# MTL_BaroTact2D_V2.net
KiCad netlist of a schematic drawn in EAGLE
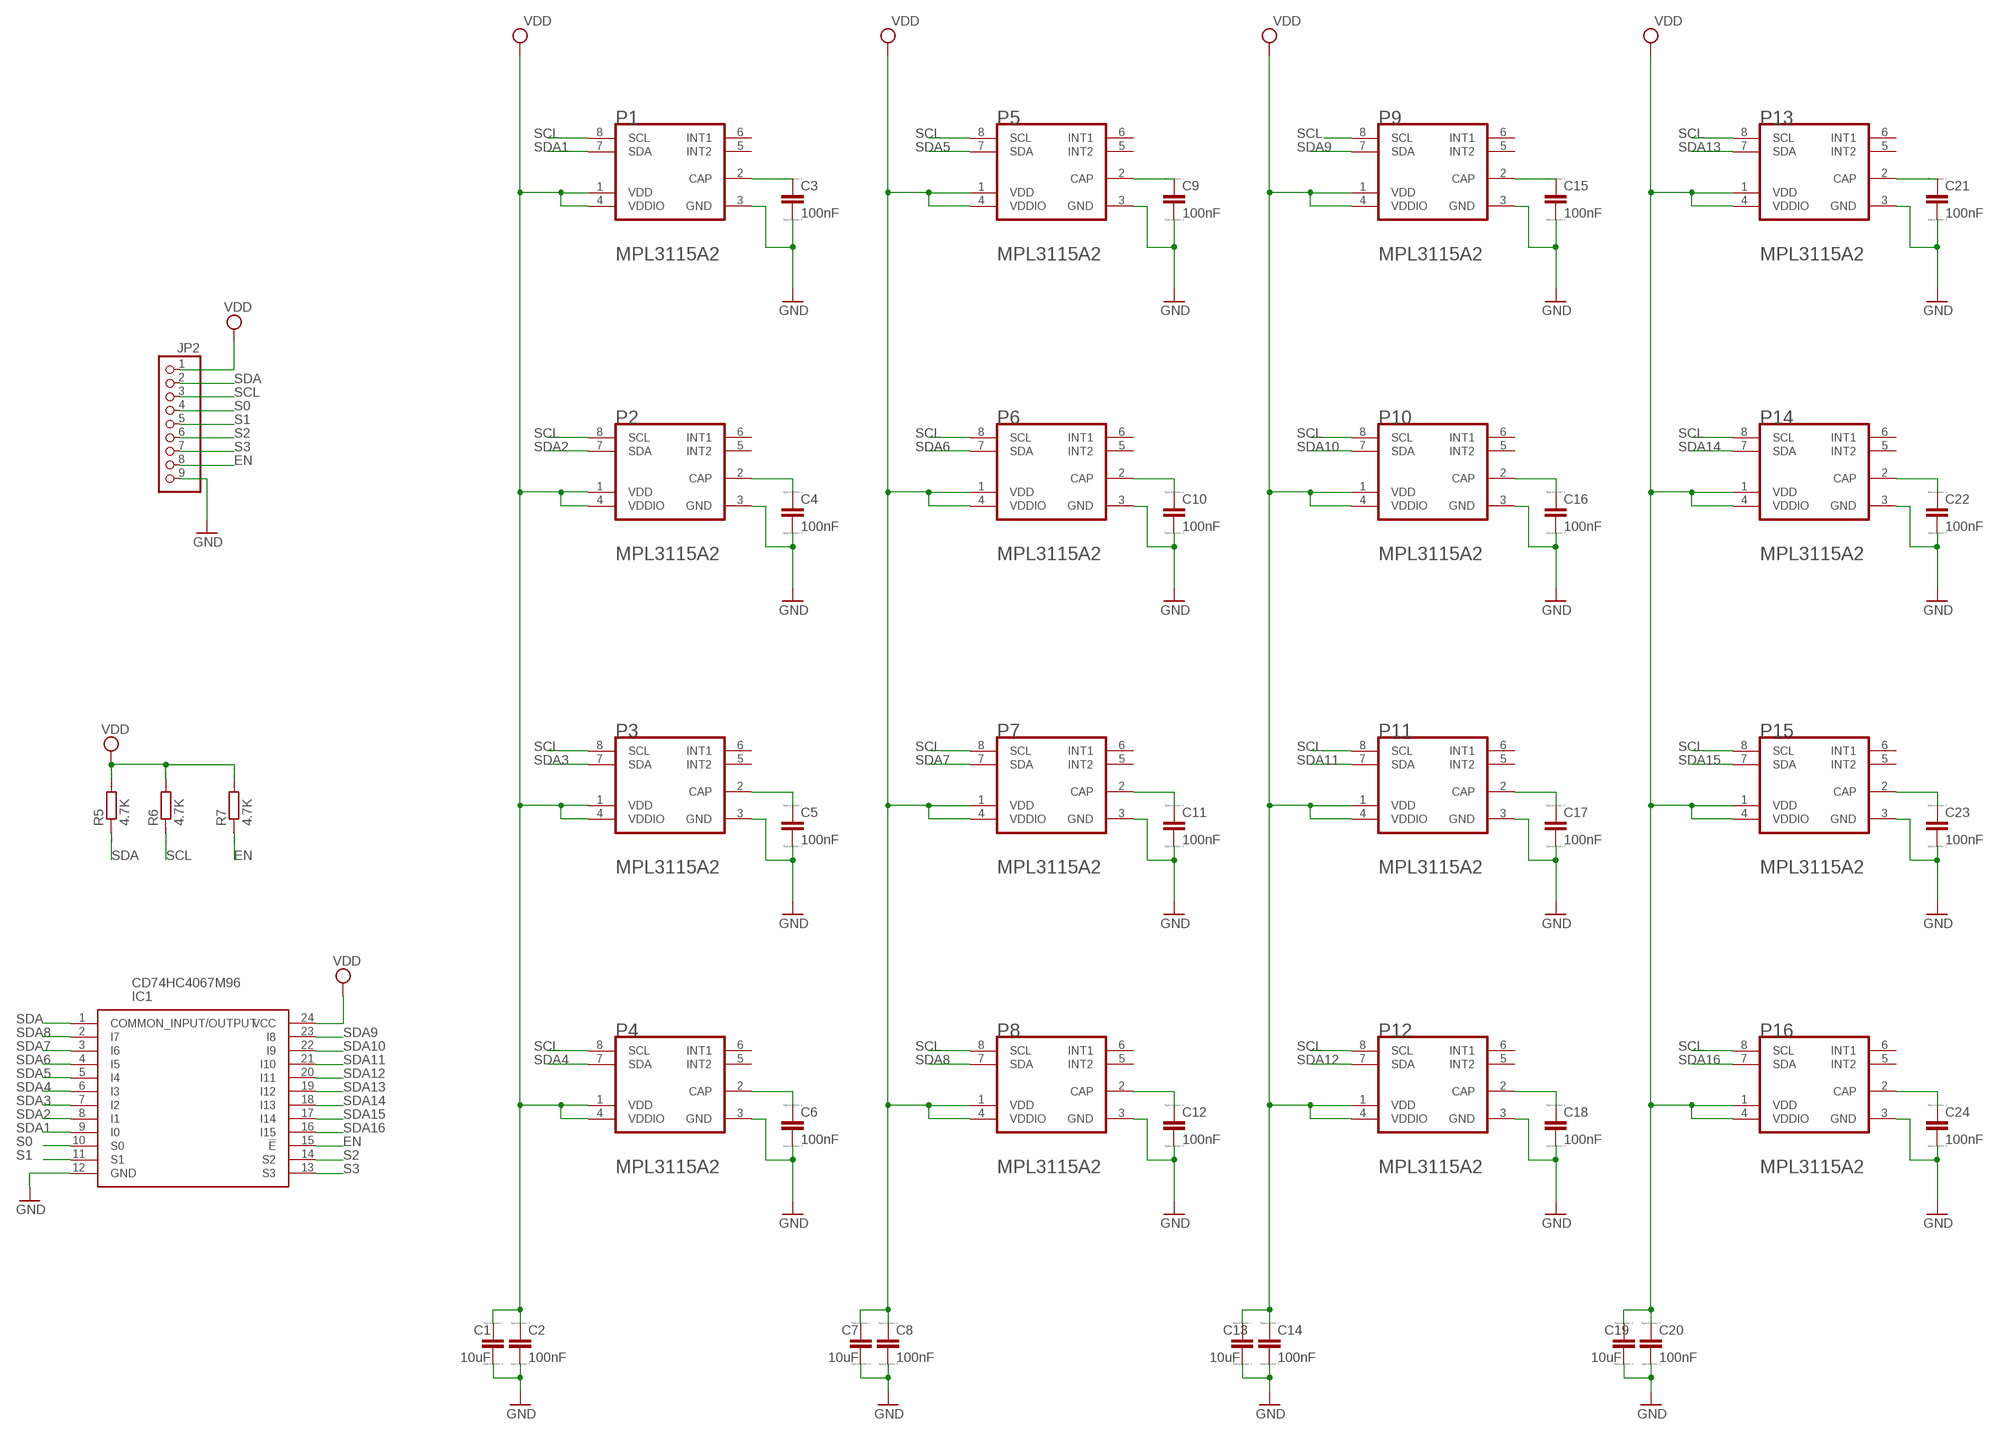
[diagram p0: schematic, sheet 1]

(export (version "E")
  (design (tool "Eeschema 10.0.6"))
  (components
    (comp (ref "C1")
      (value "10uF")
      (footprint "eagle-import:C0402")
      (libsource (lib "eagle-import") (part "CC0402"))
    )
    (comp (ref "C2")
      (value "100nF")
      (footprint "eagle-import:C0402")
      (libsource (lib "eagle-import") (part "CC0402"))
    )
    (comp (ref "C3")
      (value "100nF")
      (footprint "eagle-import:C0402")
      (libsource (lib "eagle-import") (part "CC0402"))
    )
    (comp (ref "C4")
      (value "100nF")
      (footprint "eagle-import:C0402")
      (libsource (lib "eagle-import") (part "CC0402"))
    )
    (comp (ref "C5")
      (value "100nF")
      (footprint "eagle-import:C0402")
      (libsource (lib "eagle-import") (part "CC0402"))
    )
    (comp (ref "C6")
      (value "100nF")
      (footprint "eagle-import:C0402")
      (libsource (lib "eagle-import") (part "CC0402"))
    )
    (comp (ref "C7")
      (value "10uF")
      (footprint "eagle-import:C0402")
      (libsource (lib "eagle-import") (part "CC0402"))
    )
    (comp (ref "C8")
      (value "100nF")
      (footprint "eagle-import:C0402")
      (libsource (lib "eagle-import") (part "CC0402"))
    )
    (comp (ref "C9")
      (value "100nF")
      (footprint "eagle-import:C0402")
      (libsource (lib "eagle-import") (part "CC0402"))
    )
    (comp (ref "C10")
      (value "100nF")
      (footprint "eagle-import:C0402")
      (libsource (lib "eagle-import") (part "CC0402"))
    )
    (comp (ref "C11")
      (value "100nF")
      (footprint "eagle-import:C0402")
      (libsource (lib "eagle-import") (part "CC0402"))
    )
    (comp (ref "C12")
      (value "100nF")
      (footprint "eagle-import:C0402")
      (libsource (lib "eagle-import") (part "CC0402"))
    )
    (comp (ref "C13")
      (value "10uF")
      (footprint "eagle-import:C0402")
      (libsource (lib "eagle-import") (part "CC0402"))
    )
    (comp (ref "C14")
      (value "100nF")
      (footprint "eagle-import:C0402")
      (libsource (lib "eagle-import") (part "CC0402"))
    )
    (comp (ref "C15")
      (value "100nF")
      (footprint "eagle-import:C0402")
      (libsource (lib "eagle-import") (part "CC0402"))
    )
    (comp (ref "C16")
      (value "100nF")
      (footprint "eagle-import:C0402")
      (libsource (lib "eagle-import") (part "CC0402"))
    )
    (comp (ref "C17")
      (value "100nF")
      (footprint "eagle-import:C0402")
      (libsource (lib "eagle-import") (part "CC0402"))
    )
    (comp (ref "C18")
      (value "100nF")
      (footprint "eagle-import:C0402")
      (libsource (lib "eagle-import") (part "CC0402"))
    )
    (comp (ref "C19")
      (value "10uF")
      (footprint "eagle-import:C0402")
      (libsource (lib "eagle-import") (part "CC0402"))
    )
    (comp (ref "C20")
      (value "100nF")
      (footprint "eagle-import:C0402")
      (libsource (lib "eagle-import") (part "CC0402"))
    )
    (comp (ref "C21")
      (value "100nF")
      (footprint "eagle-import:C0402")
      (libsource (lib "eagle-import") (part "CC0402"))
    )
    (comp (ref "C22")
      (value "100nF")
      (footprint "eagle-import:C0402")
      (libsource (lib "eagle-import") (part "CC0402"))
    )
    (comp (ref "C23")
      (value "100nF")
      (footprint "eagle-import:C0402")
      (libsource (lib "eagle-import") (part "CC0402"))
    )
    (comp (ref "C24")
      (value "100nF")
      (footprint "eagle-import:C0402")
      (libsource (lib "eagle-import") (part "CC0402"))
    )
    (comp (ref "IC1")
      (value "CD74HC4067M96")
      (footprint "eagle-import:SOIC127P1030X265-24N")
      (fields (field (name "MOUSER_PART_NUMBER") "595-CD74HC4067M96"))
      (libsource (lib "eagle-import") (part "CD74HC4067M96"))
    )
    (comp (ref "JP2")
      (value "PINHD-1X9")
      (footprint "eagle-import:1X09")
      (libsource (lib "eagle-import") (part "PINHD-1X9"))
    )
    (comp (ref "P1")
      (value "FREESCALE_SEMICONDUCTOR_MPL3115A2FREESCALE_SEMICONDUCTOR_MPL3115A2_0_0")
      (footprint "eagle-import:FREESCALE_SEMICONDUCTOR_MPL3115A2_0")
      (fields (field (name "MF") "Freescale Semiconductor") (field (name "MPN") "MPL3115A2"))
      (libsource (lib "eagle-import") (part "FREESCALE_SEMICONDUCTOR_MPL3115A2FREESCALE_SEMICONDUCTOR_MPL3115A2_0_0"))
    )
    (comp (ref "P2")
      (value "FREESCALE_SEMICONDUCTOR_MPL3115A2FREESCALE_SEMICONDUCTOR_MPL3115A2_0_0")
      (footprint "eagle-import:FREESCALE_SEMICONDUCTOR_MPL3115A2_0")
      (fields (field (name "MF") "Freescale Semiconductor") (field (name "MPN") "MPL3115A2"))
      (libsource (lib "eagle-import") (part "FREESCALE_SEMICONDUCTOR_MPL3115A2FREESCALE_SEMICONDUCTOR_MPL3115A2_0_0"))
    )
    (comp (ref "P3")
      (value "FREESCALE_SEMICONDUCTOR_MPL3115A2FREESCALE_SEMICONDUCTOR_MPL3115A2_0_0")
      (footprint "eagle-import:FREESCALE_SEMICONDUCTOR_MPL3115A2_0")
      (fields (field (name "MF") "Freescale Semiconductor") (field (name "MPN") "MPL3115A2"))
      (libsource (lib "eagle-import") (part "FREESCALE_SEMICONDUCTOR_MPL3115A2FREESCALE_SEMICONDUCTOR_MPL3115A2_0_0"))
    )
    (comp (ref "P4")
      (value "FREESCALE_SEMICONDUCTOR_MPL3115A2FREESCALE_SEMICONDUCTOR_MPL3115A2_0_0")
      (footprint "eagle-import:FREESCALE_SEMICONDUCTOR_MPL3115A2_0")
      (fields (field (name "MF") "Freescale Semiconductor") (field (name "MPN") "MPL3115A2"))
      (libsource (lib "eagle-import") (part "FREESCALE_SEMICONDUCTOR_MPL3115A2FREESCALE_SEMICONDUCTOR_MPL3115A2_0_0"))
    )
    (comp (ref "P5")
      (value "FREESCALE_SEMICONDUCTOR_MPL3115A2FREESCALE_SEMICONDUCTOR_MPL3115A2_0_0")
      (footprint "eagle-import:FREESCALE_SEMICONDUCTOR_MPL3115A2_0")
      (fields (field (name "MF") "Freescale Semiconductor") (field (name "MPN") "MPL3115A2"))
      (libsource (lib "eagle-import") (part "FREESCALE_SEMICONDUCTOR_MPL3115A2FREESCALE_SEMICONDUCTOR_MPL3115A2_0_0"))
    )
    (comp (ref "P6")
      (value "FREESCALE_SEMICONDUCTOR_MPL3115A2FREESCALE_SEMICONDUCTOR_MPL3115A2_0_0")
      (footprint "eagle-import:FREESCALE_SEMICONDUCTOR_MPL3115A2_0")
      (fields (field (name "MF") "Freescale Semiconductor") (field (name "MPN") "MPL3115A2"))
      (libsource (lib "eagle-import") (part "FREESCALE_SEMICONDUCTOR_MPL3115A2FREESCALE_SEMICONDUCTOR_MPL3115A2_0_0"))
    )
    (comp (ref "P7")
      (value "FREESCALE_SEMICONDUCTOR_MPL3115A2FREESCALE_SEMICONDUCTOR_MPL3115A2_0_0")
      (footprint "eagle-import:FREESCALE_SEMICONDUCTOR_MPL3115A2_0")
      (fields (field (name "MF") "Freescale Semiconductor") (field (name "MPN") "MPL3115A2"))
      (libsource (lib "eagle-import") (part "FREESCALE_SEMICONDUCTOR_MPL3115A2FREESCALE_SEMICONDUCTOR_MPL3115A2_0_0"))
    )
    (comp (ref "P8")
      (value "FREESCALE_SEMICONDUCTOR_MPL3115A2FREESCALE_SEMICONDUCTOR_MPL3115A2_0_0")
      (footprint "eagle-import:FREESCALE_SEMICONDUCTOR_MPL3115A2_0")
      (fields (field (name "MF") "Freescale Semiconductor") (field (name "MPN") "MPL3115A2"))
      (libsource (lib "eagle-import") (part "FREESCALE_SEMICONDUCTOR_MPL3115A2FREESCALE_SEMICONDUCTOR_MPL3115A2_0_0"))
    )
    (comp (ref "P9")
      (value "FREESCALE_SEMICONDUCTOR_MPL3115A2FREESCALE_SEMICONDUCTOR_MPL3115A2_0_0")
      (footprint "eagle-import:FREESCALE_SEMICONDUCTOR_MPL3115A2_0")
      (fields (field (name "MF") "Freescale Semiconductor") (field (name "MPN") "MPL3115A2"))
      (libsource (lib "eagle-import") (part "FREESCALE_SEMICONDUCTOR_MPL3115A2FREESCALE_SEMICONDUCTOR_MPL3115A2_0_0"))
    )
    (comp (ref "P10")
      (value "FREESCALE_SEMICONDUCTOR_MPL3115A2FREESCALE_SEMICONDUCTOR_MPL3115A2_0_0")
      (footprint "eagle-import:FREESCALE_SEMICONDUCTOR_MPL3115A2_0")
      (fields (field (name "MF") "Freescale Semiconductor") (field (name "MPN") "MPL3115A2"))
      (libsource (lib "eagle-import") (part "FREESCALE_SEMICONDUCTOR_MPL3115A2FREESCALE_SEMICONDUCTOR_MPL3115A2_0_0"))
    )
    (comp (ref "P11")
      (value "FREESCALE_SEMICONDUCTOR_MPL3115A2FREESCALE_SEMICONDUCTOR_MPL3115A2_0_0")
      (footprint "eagle-import:FREESCALE_SEMICONDUCTOR_MPL3115A2_0")
      (fields (field (name "MF") "Freescale Semiconductor") (field (name "MPN") "MPL3115A2"))
      (libsource (lib "eagle-import") (part "FREESCALE_SEMICONDUCTOR_MPL3115A2FREESCALE_SEMICONDUCTOR_MPL3115A2_0_0"))
    )
    (comp (ref "P12")
      (value "FREESCALE_SEMICONDUCTOR_MPL3115A2FREESCALE_SEMICONDUCTOR_MPL3115A2_0_0")
      (footprint "eagle-import:FREESCALE_SEMICONDUCTOR_MPL3115A2_0")
      (fields (field (name "MF") "Freescale Semiconductor") (field (name "MPN") "MPL3115A2"))
      (libsource (lib "eagle-import") (part "FREESCALE_SEMICONDUCTOR_MPL3115A2FREESCALE_SEMICONDUCTOR_MPL3115A2_0_0"))
    )
    (comp (ref "P13")
      (value "FREESCALE_SEMICONDUCTOR_MPL3115A2FREESCALE_SEMICONDUCTOR_MPL3115A2_0_0")
      (footprint "eagle-import:FREESCALE_SEMICONDUCTOR_MPL3115A2_0")
      (fields (field (name "MF") "Freescale Semiconductor") (field (name "MPN") "MPL3115A2"))
      (libsource (lib "eagle-import") (part "FREESCALE_SEMICONDUCTOR_MPL3115A2FREESCALE_SEMICONDUCTOR_MPL3115A2_0_0"))
    )
    (comp (ref "P14")
      (value "FREESCALE_SEMICONDUCTOR_MPL3115A2FREESCALE_SEMICONDUCTOR_MPL3115A2_0_0")
      (footprint "eagle-import:FREESCALE_SEMICONDUCTOR_MPL3115A2_0")
      (fields (field (name "MF") "Freescale Semiconductor") (field (name "MPN") "MPL3115A2"))
      (libsource (lib "eagle-import") (part "FREESCALE_SEMICONDUCTOR_MPL3115A2FREESCALE_SEMICONDUCTOR_MPL3115A2_0_0"))
    )
    (comp (ref "P15")
      (value "FREESCALE_SEMICONDUCTOR_MPL3115A2FREESCALE_SEMICONDUCTOR_MPL3115A2_0_0")
      (footprint "eagle-import:FREESCALE_SEMICONDUCTOR_MPL3115A2_0")
      (fields (field (name "MF") "Freescale Semiconductor") (field (name "MPN") "MPL3115A2"))
      (libsource (lib "eagle-import") (part "FREESCALE_SEMICONDUCTOR_MPL3115A2FREESCALE_SEMICONDUCTOR_MPL3115A2_0_0"))
    )
    (comp (ref "P16")
      (value "FREESCALE_SEMICONDUCTOR_MPL3115A2FREESCALE_SEMICONDUCTOR_MPL3115A2_0_0")
      (footprint "eagle-import:FREESCALE_SEMICONDUCTOR_MPL3115A2_0")
      (fields (field (name "MF") "Freescale Semiconductor") (field (name "MPN") "MPL3115A2"))
      (libsource (lib "eagle-import") (part "FREESCALE_SEMICONDUCTOR_MPL3115A2FREESCALE_SEMICONDUCTOR_MPL3115A2_0_0"))
    )
    (comp (ref "R5")
      (value "4.7K")
      (footprint "eagle-import:R0603")
      (libsource (lib "eagle-import") (part "RR0603"))
    )
    (comp (ref "R6")
      (value "4.7K")
      (footprint "eagle-import:R0603")
      (libsource (lib "eagle-import") (part "RR0603"))
    )
    (comp (ref "R7")
      (value "4.7K")
      (footprint "eagle-import:R0603")
      (libsource (lib "eagle-import") (part "RR0603"))
    )
  )
  (nets
    (net (code "1") (name "/EN") (class "Default")
      (node (ref "IC1") (pin "15") (pinfunction "~{E}_15") (pintype "bidirectional"))
      (node (ref "JP2") (pin "8") (pinfunction "8_8") (pintype "passive"))
      (node (ref "R7") (pin "1") (pinfunction "1_1") (pintype "passive"))
    )
    (net (code "2") (name "/S0") (class "Default")
      (node (ref "IC1") (pin "10") (pinfunction "S0_10") (pintype "bidirectional"))
      (node (ref "JP2") (pin "4") (pinfunction "4_4") (pintype "passive"))
    )
    (net (code "3") (name "/S1") (class "Default")
      (node (ref "IC1") (pin "11") (pinfunction "S1_11") (pintype "bidirectional"))
      (node (ref "JP2") (pin "5") (pinfunction "5_5") (pintype "passive"))
    )
    (net (code "4") (name "/S2") (class "Default")
      (node (ref "IC1") (pin "14") (pinfunction "S2_14") (pintype "bidirectional"))
      (node (ref "JP2") (pin "6") (pinfunction "6_6") (pintype "passive"))
    )
    (net (code "5") (name "/S3") (class "Default")
      (node (ref "IC1") (pin "13") (pinfunction "S3_13") (pintype "bidirectional"))
      (node (ref "JP2") (pin "7") (pinfunction "7_7") (pintype "passive"))
    )
    (net (code "6") (name "/SCL") (class "Default")
      (node (ref "JP2") (pin "3") (pinfunction "3_3") (pintype "passive"))
      (node (ref "P1") (pin "8") (pinfunction "SCL_8") (pintype "input"))
      (node (ref "P10") (pin "8") (pinfunction "SCL_8") (pintype "input"))
      (node (ref "P11") (pin "8") (pinfunction "SCL_8") (pintype "input"))
      (node (ref "P12") (pin "8") (pinfunction "SCL_8") (pintype "input"))
      (node (ref "P13") (pin "8") (pinfunction "SCL_8") (pintype "input"))
      (node (ref "P14") (pin "8") (pinfunction "SCL_8") (pintype "input"))
      (node (ref "P15") (pin "8") (pinfunction "SCL_8") (pintype "input"))
      (node (ref "P16") (pin "8") (pinfunction "SCL_8") (pintype "input"))
      (node (ref "P2") (pin "8") (pinfunction "SCL_8") (pintype "input"))
      (node (ref "P3") (pin "8") (pinfunction "SCL_8") (pintype "input"))
      (node (ref "P4") (pin "8") (pinfunction "SCL_8") (pintype "input"))
      (node (ref "P5") (pin "8") (pinfunction "SCL_8") (pintype "input"))
      (node (ref "P6") (pin "8") (pinfunction "SCL_8") (pintype "input"))
      (node (ref "P7") (pin "8") (pinfunction "SCL_8") (pintype "input"))
      (node (ref "P8") (pin "8") (pinfunction "SCL_8") (pintype "input"))
      (node (ref "P9") (pin "8") (pinfunction "SCL_8") (pintype "input"))
      (node (ref "R6") (pin "1") (pinfunction "1_1") (pintype "passive"))
    )
    (net (code "7") (name "/SDA") (class "Default")
      (node (ref "IC1") (pin "1") (pinfunction "COMMON_INPUT/OUTPUT_1") (pintype "bidirectional"))
      (node (ref "JP2") (pin "2") (pinfunction "2_2") (pintype "passive"))
      (node (ref "R5") (pin "1") (pinfunction "1_1") (pintype "passive"))
    )
    (net (code "8") (name "/SDA1") (class "Default")
      (node (ref "IC1") (pin "9") (pinfunction "I0_9") (pintype "bidirectional"))
      (node (ref "P1") (pin "7") (pinfunction "SDA_7") (pintype "bidirectional"))
    )
    (net (code "9") (name "/SDA2") (class "Default")
      (node (ref "IC1") (pin "8") (pinfunction "I1_8") (pintype "bidirectional"))
      (node (ref "P2") (pin "7") (pinfunction "SDA_7") (pintype "bidirectional"))
    )
    (net (code "10") (name "/SDA3") (class "Default")
      (node (ref "IC1") (pin "7") (pinfunction "I2_7") (pintype "bidirectional"))
      (node (ref "P3") (pin "7") (pinfunction "SDA_7") (pintype "bidirectional"))
    )
    (net (code "11") (name "/SDA4") (class "Default")
      (node (ref "IC1") (pin "6") (pinfunction "I3_6") (pintype "bidirectional"))
      (node (ref "P4") (pin "7") (pinfunction "SDA_7") (pintype "bidirectional"))
    )
    (net (code "12") (name "/SDA5") (class "Default")
      (node (ref "IC1") (pin "5") (pinfunction "I4_5") (pintype "bidirectional"))
      (node (ref "P5") (pin "7") (pinfunction "SDA_7") (pintype "bidirectional"))
    )
    (net (code "13") (name "/SDA6") (class "Default")
      (node (ref "IC1") (pin "4") (pinfunction "I5_4") (pintype "bidirectional"))
      (node (ref "P6") (pin "7") (pinfunction "SDA_7") (pintype "bidirectional"))
    )
    (net (code "14") (name "/SDA7") (class "Default")
      (node (ref "IC1") (pin "3") (pinfunction "I6_3") (pintype "bidirectional"))
      (node (ref "P7") (pin "7") (pinfunction "SDA_7") (pintype "bidirectional"))
    )
    (net (code "15") (name "/SDA8") (class "Default")
      (node (ref "IC1") (pin "2") (pinfunction "I7_2") (pintype "bidirectional"))
      (node (ref "P8") (pin "7") (pinfunction "SDA_7") (pintype "bidirectional"))
    )
    (net (code "16") (name "/SDA9") (class "Default")
      (node (ref "IC1") (pin "23") (pinfunction "I8_23") (pintype "bidirectional"))
      (node (ref "P9") (pin "7") (pinfunction "SDA_7") (pintype "bidirectional"))
    )
    (net (code "17") (name "/SDA10") (class "Default")
      (node (ref "IC1") (pin "22") (pinfunction "I9_22") (pintype "bidirectional"))
      (node (ref "P10") (pin "7") (pinfunction "SDA_7") (pintype "bidirectional"))
    )
    (net (code "18") (name "/SDA11") (class "Default")
      (node (ref "IC1") (pin "21") (pinfunction "I10_21") (pintype "bidirectional"))
      (node (ref "P11") (pin "7") (pinfunction "SDA_7") (pintype "bidirectional"))
    )
    (net (code "19") (name "/SDA12") (class "Default")
      (node (ref "IC1") (pin "20") (pinfunction "I11_20") (pintype "bidirectional"))
      (node (ref "P12") (pin "7") (pinfunction "SDA_7") (pintype "bidirectional"))
    )
    (net (code "20") (name "/SDA13") (class "Default")
      (node (ref "IC1") (pin "19") (pinfunction "I12_19") (pintype "bidirectional"))
      (node (ref "P13") (pin "7") (pinfunction "SDA_7") (pintype "bidirectional"))
    )
    (net (code "21") (name "/SDA14") (class "Default")
      (node (ref "IC1") (pin "18") (pinfunction "I13_18") (pintype "bidirectional"))
      (node (ref "P14") (pin "7") (pinfunction "SDA_7") (pintype "bidirectional"))
    )
    (net (code "22") (name "/SDA15") (class "Default")
      (node (ref "IC1") (pin "17") (pinfunction "I14_17") (pintype "bidirectional"))
      (node (ref "P15") (pin "7") (pinfunction "SDA_7") (pintype "bidirectional"))
    )
    (net (code "23") (name "/SDA16") (class "Default")
      (node (ref "IC1") (pin "16") (pinfunction "I15_16") (pintype "bidirectional"))
      (node (ref "P16") (pin "7") (pinfunction "SDA_7") (pintype "bidirectional"))
    )
    (net (code "24") (name "GND") (class "Default")
      (node (ref "C1") (pin "2") (pinfunction "2_2") (pintype "passive"))
      (node (ref "C10") (pin "2") (pinfunction "2_2") (pintype "passive"))
      (node (ref "C11") (pin "2") (pinfunction "2_2") (pintype "passive"))
      (node (ref "C12") (pin "2") (pinfunction "2_2") (pintype "passive"))
      (node (ref "C13") (pin "2") (pinfunction "2_2") (pintype "passive"))
      (node (ref "C14") (pin "2") (pinfunction "2_2") (pintype "passive"))
      (node (ref "C15") (pin "2") (pinfunction "2_2") (pintype "passive"))
      (node (ref "C16") (pin "2") (pinfunction "2_2") (pintype "passive"))
      (node (ref "C17") (pin "2") (pinfunction "2_2") (pintype "passive"))
      (node (ref "C18") (pin "2") (pinfunction "2_2") (pintype "passive"))
      (node (ref "C19") (pin "2") (pinfunction "2_2") (pintype "passive"))
      (node (ref "C2") (pin "2") (pinfunction "2_2") (pintype "passive"))
      (node (ref "C20") (pin "2") (pinfunction "2_2") (pintype "passive"))
      (node (ref "C21") (pin "2") (pinfunction "2_2") (pintype "passive"))
      (node (ref "C22") (pin "2") (pinfunction "2_2") (pintype "passive"))
      (node (ref "C23") (pin "2") (pinfunction "2_2") (pintype "passive"))
      (node (ref "C24") (pin "2") (pinfunction "2_2") (pintype "passive"))
      (node (ref "C3") (pin "2") (pinfunction "2_2") (pintype "passive"))
      (node (ref "C4") (pin "2") (pinfunction "2_2") (pintype "passive"))
      (node (ref "C5") (pin "2") (pinfunction "2_2") (pintype "passive"))
      (node (ref "C6") (pin "2") (pinfunction "2_2") (pintype "passive"))
      (node (ref "C7") (pin "2") (pinfunction "2_2") (pintype "passive"))
      (node (ref "C8") (pin "2") (pinfunction "2_2") (pintype "passive"))
      (node (ref "C9") (pin "2") (pinfunction "2_2") (pintype "passive"))
      (node (ref "IC1") (pin "12") (pinfunction "GND_12") (pintype "bidirectional"))
      (node (ref "JP2") (pin "9") (pinfunction "9_9") (pintype "passive"))
      (node (ref "P1") (pin "3") (pinfunction "GND_3") (pintype "power_in"))
      (node (ref "P10") (pin "3") (pinfunction "GND_3") (pintype "power_in"))
      (node (ref "P11") (pin "3") (pinfunction "GND_3") (pintype "power_in"))
      (node (ref "P12") (pin "3") (pinfunction "GND_3") (pintype "power_in"))
      (node (ref "P13") (pin "3") (pinfunction "GND_3") (pintype "power_in"))
      (node (ref "P14") (pin "3") (pinfunction "GND_3") (pintype "power_in"))
      (node (ref "P15") (pin "3") (pinfunction "GND_3") (pintype "power_in"))
      (node (ref "P16") (pin "3") (pinfunction "GND_3") (pintype "power_in"))
      (node (ref "P2") (pin "3") (pinfunction "GND_3") (pintype "power_in"))
      (node (ref "P3") (pin "3") (pinfunction "GND_3") (pintype "power_in"))
      (node (ref "P4") (pin "3") (pinfunction "GND_3") (pintype "power_in"))
      (node (ref "P5") (pin "3") (pinfunction "GND_3") (pintype "power_in"))
      (node (ref "P6") (pin "3") (pinfunction "GND_3") (pintype "power_in"))
      (node (ref "P7") (pin "3") (pinfunction "GND_3") (pintype "power_in"))
      (node (ref "P8") (pin "3") (pinfunction "GND_3") (pintype "power_in"))
      (node (ref "P9") (pin "3") (pinfunction "GND_3") (pintype "power_in"))
    )
    (net (code "25") (name "Net-(P1-CAP)") (class "Default")
      (node (ref "C3") (pin "1") (pinfunction "1_1") (pintype "passive"))
      (node (ref "P1") (pin "2") (pinfunction "CAP_2") (pintype "passive"))
    )
    (net (code "26") (name "Net-(P2-CAP)") (class "Default")
      (node (ref "C4") (pin "1") (pinfunction "1_1") (pintype "passive"))
      (node (ref "P2") (pin "2") (pinfunction "CAP_2") (pintype "passive"))
    )
    (net (code "27") (name "Net-(P3-CAP)") (class "Default")
      (node (ref "C5") (pin "1") (pinfunction "1_1") (pintype "passive"))
      (node (ref "P3") (pin "2") (pinfunction "CAP_2") (pintype "passive"))
    )
    (net (code "28") (name "Net-(P4-CAP)") (class "Default")
      (node (ref "C6") (pin "1") (pinfunction "1_1") (pintype "passive"))
      (node (ref "P4") (pin "2") (pinfunction "CAP_2") (pintype "passive"))
    )
    (net (code "29") (name "Net-(P5-CAP)") (class "Default")
      (node (ref "C9") (pin "1") (pinfunction "1_1") (pintype "passive"))
      (node (ref "P5") (pin "2") (pinfunction "CAP_2") (pintype "passive"))
    )
    (net (code "30") (name "Net-(P6-CAP)") (class "Default")
      (node (ref "C10") (pin "1") (pinfunction "1_1") (pintype "passive"))
      (node (ref "P6") (pin "2") (pinfunction "CAP_2") (pintype "passive"))
    )
    (net (code "31") (name "Net-(P7-CAP)") (class "Default")
      (node (ref "C11") (pin "1") (pinfunction "1_1") (pintype "passive"))
      (node (ref "P7") (pin "2") (pinfunction "CAP_2") (pintype "passive"))
    )
    (net (code "32") (name "Net-(P8-CAP)") (class "Default")
      (node (ref "C12") (pin "1") (pinfunction "1_1") (pintype "passive"))
      (node (ref "P8") (pin "2") (pinfunction "CAP_2") (pintype "passive"))
    )
    (net (code "33") (name "Net-(P9-CAP)") (class "Default")
      (node (ref "C15") (pin "1") (pinfunction "1_1") (pintype "passive"))
      (node (ref "P9") (pin "2") (pinfunction "CAP_2") (pintype "passive"))
    )
    (net (code "34") (name "Net-(P10-CAP)") (class "Default")
      (node (ref "C16") (pin "1") (pinfunction "1_1") (pintype "passive"))
      (node (ref "P10") (pin "2") (pinfunction "CAP_2") (pintype "passive"))
    )
    (net (code "35") (name "Net-(P11-CAP)") (class "Default")
      (node (ref "C17") (pin "1") (pinfunction "1_1") (pintype "passive"))
      (node (ref "P11") (pin "2") (pinfunction "CAP_2") (pintype "passive"))
    )
    (net (code "36") (name "Net-(P12-CAP)") (class "Default")
      (node (ref "C18") (pin "1") (pinfunction "1_1") (pintype "passive"))
      (node (ref "P12") (pin "2") (pinfunction "CAP_2") (pintype "passive"))
    )
    (net (code "37") (name "Net-(P13-CAP)") (class "Default")
      (node (ref "C21") (pin "1") (pinfunction "1_1") (pintype "passive"))
      (node (ref "P13") (pin "2") (pinfunction "CAP_2") (pintype "passive"))
    )
    (net (code "38") (name "Net-(P14-CAP)") (class "Default")
      (node (ref "C22") (pin "1") (pinfunction "1_1") (pintype "passive"))
      (node (ref "P14") (pin "2") (pinfunction "CAP_2") (pintype "passive"))
    )
    (net (code "39") (name "Net-(P15-CAP)") (class "Default")
      (node (ref "C23") (pin "1") (pinfunction "1_1") (pintype "passive"))
      (node (ref "P15") (pin "2") (pinfunction "CAP_2") (pintype "passive"))
    )
    (net (code "40") (name "Net-(P16-CAP)") (class "Default")
      (node (ref "C24") (pin "1") (pinfunction "1_1") (pintype "passive"))
      (node (ref "P16") (pin "2") (pinfunction "CAP_2") (pintype "passive"))
    )
    (net (code "41") (name "VDD") (class "Default")
      (node (ref "C1") (pin "1") (pinfunction "1_1") (pintype "passive"))
      (node (ref "C13") (pin "1") (pinfunction "1_1") (pintype "passive"))
      (node (ref "C14") (pin "1") (pinfunction "1_1") (pintype "passive"))
      (node (ref "C19") (pin "1") (pinfunction "1_1") (pintype "passive"))
      (node (ref "C2") (pin "1") (pinfunction "1_1") (pintype "passive"))
      (node (ref "C20") (pin "1") (pinfunction "1_1") (pintype "passive"))
      (node (ref "C7") (pin "1") (pinfunction "1_1") (pintype "passive"))
      (node (ref "C8") (pin "1") (pinfunction "1_1") (pintype "passive"))
      (node (ref "IC1") (pin "24") (pinfunction "VCC_24") (pintype "bidirectional"))
      (node (ref "JP2") (pin "1") (pinfunction "1_1") (pintype "passive"))
      (node (ref "P1") (pin "1") (pinfunction "VDD_1") (pintype "power_in"))
      (node (ref "P1") (pin "4") (pinfunction "VDDIO_4") (pintype "power_in"))
      (node (ref "P10") (pin "1") (pinfunction "VDD_1") (pintype "power_in"))
      (node (ref "P10") (pin "4") (pinfunction "VDDIO_4") (pintype "power_in"))
      (node (ref "P11") (pin "1") (pinfunction "VDD_1") (pintype "power_in"))
      (node (ref "P11") (pin "4") (pinfunction "VDDIO_4") (pintype "power_in"))
      (node (ref "P12") (pin "1") (pinfunction "VDD_1") (pintype "power_in"))
      (node (ref "P12") (pin "4") (pinfunction "VDDIO_4") (pintype "power_in"))
      (node (ref "P13") (pin "1") (pinfunction "VDD_1") (pintype "power_in"))
      (node (ref "P13") (pin "4") (pinfunction "VDDIO_4") (pintype "power_in"))
      (node (ref "P14") (pin "1") (pinfunction "VDD_1") (pintype "power_in"))
      (node (ref "P14") (pin "4") (pinfunction "VDDIO_4") (pintype "power_in"))
      (node (ref "P15") (pin "1") (pinfunction "VDD_1") (pintype "power_in"))
      (node (ref "P15") (pin "4") (pinfunction "VDDIO_4") (pintype "power_in"))
      (node (ref "P16") (pin "1") (pinfunction "VDD_1") (pintype "power_in"))
      (node (ref "P16") (pin "4") (pinfunction "VDDIO_4") (pintype "power_in"))
      (node (ref "P2") (pin "1") (pinfunction "VDD_1") (pintype "power_in"))
      (node (ref "P2") (pin "4") (pinfunction "VDDIO_4") (pintype "power_in"))
      (node (ref "P3") (pin "1") (pinfunction "VDD_1") (pintype "power_in"))
      (node (ref "P3") (pin "4") (pinfunction "VDDIO_4") (pintype "power_in"))
      (node (ref "P4") (pin "1") (pinfunction "VDD_1") (pintype "power_in"))
      (node (ref "P4") (pin "4") (pinfunction "VDDIO_4") (pintype "power_in"))
      (node (ref "P5") (pin "1") (pinfunction "VDD_1") (pintype "power_in"))
      (node (ref "P5") (pin "4") (pinfunction "VDDIO_4") (pintype "power_in"))
      (node (ref "P6") (pin "1") (pinfunction "VDD_1") (pintype "power_in"))
      (node (ref "P6") (pin "4") (pinfunction "VDDIO_4") (pintype "power_in"))
      (node (ref "P7") (pin "1") (pinfunction "VDD_1") (pintype "power_in"))
      (node (ref "P7") (pin "4") (pinfunction "VDDIO_4") (pintype "power_in"))
      (node (ref "P8") (pin "1") (pinfunction "VDD_1") (pintype "power_in"))
      (node (ref "P8") (pin "4") (pinfunction "VDDIO_4") (pintype "power_in"))
      (node (ref "P9") (pin "1") (pinfunction "VDD_1") (pintype "power_in"))
      (node (ref "P9") (pin "4") (pinfunction "VDDIO_4") (pintype "power_in"))
      (node (ref "R5") (pin "2") (pinfunction "2_2") (pintype "passive"))
      (node (ref "R6") (pin "2") (pinfunction "2_2") (pintype "passive"))
      (node (ref "R7") (pin "2") (pinfunction "2_2") (pintype "passive"))
    )
    (net (code "42") (name "unconnected-(P1-INT1-Pad6)") (class "Default")
      (node (ref "P1") (pin "6") (pinfunction "INT1_6") (pintype "output"))
    )
    (net (code "43") (name "unconnected-(P1-INT2-Pad5)") (class "Default")
      (node (ref "P1") (pin "5") (pinfunction "INT2_5") (pintype "output"))
    )
    (net (code "44") (name "unconnected-(P2-INT1-Pad6)") (class "Default")
      (node (ref "P2") (pin "6") (pinfunction "INT1_6") (pintype "output"))
    )
    (net (code "45") (name "unconnected-(P2-INT2-Pad5)") (class "Default")
      (node (ref "P2") (pin "5") (pinfunction "INT2_5") (pintype "output"))
    )
    (net (code "46") (name "unconnected-(P3-INT1-Pad6)") (class "Default")
      (node (ref "P3") (pin "6") (pinfunction "INT1_6") (pintype "output"))
    )
    (net (code "47") (name "unconnected-(P3-INT2-Pad5)") (class "Default")
      (node (ref "P3") (pin "5") (pinfunction "INT2_5") (pintype "output"))
    )
    (net (code "48") (name "unconnected-(P4-INT1-Pad6)") (class "Default")
      (node (ref "P4") (pin "6") (pinfunction "INT1_6") (pintype "output"))
    )
    (net (code "49") (name "unconnected-(P4-INT2-Pad5)") (class "Default")
      (node (ref "P4") (pin "5") (pinfunction "INT2_5") (pintype "output"))
    )
    (net (code "50") (name "unconnected-(P5-INT1-Pad6)") (class "Default")
      (node (ref "P5") (pin "6") (pinfunction "INT1_6") (pintype "output"))
    )
    (net (code "51") (name "unconnected-(P5-INT2-Pad5)") (class "Default")
      (node (ref "P5") (pin "5") (pinfunction "INT2_5") (pintype "output"))
    )
    (net (code "52") (name "unconnected-(P6-INT1-Pad6)") (class "Default")
      (node (ref "P6") (pin "6") (pinfunction "INT1_6") (pintype "output"))
    )
    (net (code "53") (name "unconnected-(P6-INT2-Pad5)") (class "Default")
      (node (ref "P6") (pin "5") (pinfunction "INT2_5") (pintype "output"))
    )
    (net (code "54") (name "unconnected-(P7-INT1-Pad6)") (class "Default")
      (node (ref "P7") (pin "6") (pinfunction "INT1_6") (pintype "output"))
    )
    (net (code "55") (name "unconnected-(P7-INT2-Pad5)") (class "Default")
      (node (ref "P7") (pin "5") (pinfunction "INT2_5") (pintype "output"))
    )
    (net (code "56") (name "unconnected-(P8-INT1-Pad6)") (class "Default")
      (node (ref "P8") (pin "6") (pinfunction "INT1_6") (pintype "output"))
    )
    (net (code "57") (name "unconnected-(P8-INT2-Pad5)") (class "Default")
      (node (ref "P8") (pin "5") (pinfunction "INT2_5") (pintype "output"))
    )
    (net (code "58") (name "unconnected-(P9-INT1-Pad6)") (class "Default")
      (node (ref "P9") (pin "6") (pinfunction "INT1_6") (pintype "output"))
    )
    (net (code "59") (name "unconnected-(P9-INT2-Pad5)") (class "Default")
      (node (ref "P9") (pin "5") (pinfunction "INT2_5") (pintype "output"))
    )
    (net (code "60") (name "unconnected-(P10-INT1-Pad6)") (class "Default")
      (node (ref "P10") (pin "6") (pinfunction "INT1_6") (pintype "output"))
    )
    (net (code "61") (name "unconnected-(P10-INT2-Pad5)") (class "Default")
      (node (ref "P10") (pin "5") (pinfunction "INT2_5") (pintype "output"))
    )
    (net (code "62") (name "unconnected-(P11-INT1-Pad6)") (class "Default")
      (node (ref "P11") (pin "6") (pinfunction "INT1_6") (pintype "output"))
    )
    (net (code "63") (name "unconnected-(P11-INT2-Pad5)") (class "Default")
      (node (ref "P11") (pin "5") (pinfunction "INT2_5") (pintype "output"))
    )
    (net (code "64") (name "unconnected-(P12-INT1-Pad6)") (class "Default")
      (node (ref "P12") (pin "6") (pinfunction "INT1_6") (pintype "output"))
    )
    (net (code "65") (name "unconnected-(P12-INT2-Pad5)") (class "Default")
      (node (ref "P12") (pin "5") (pinfunction "INT2_5") (pintype "output"))
    )
    (net (code "66") (name "unconnected-(P13-INT1-Pad6)") (class "Default")
      (node (ref "P13") (pin "6") (pinfunction "INT1_6") (pintype "output"))
    )
    (net (code "67") (name "unconnected-(P13-INT2-Pad5)") (class "Default")
      (node (ref "P13") (pin "5") (pinfunction "INT2_5") (pintype "output"))
    )
    (net (code "68") (name "unconnected-(P14-INT1-Pad6)") (class "Default")
      (node (ref "P14") (pin "6") (pinfunction "INT1_6") (pintype "output"))
    )
    (net (code "69") (name "unconnected-(P14-INT2-Pad5)") (class "Default")
      (node (ref "P14") (pin "5") (pinfunction "INT2_5") (pintype "output"))
    )
    (net (code "70") (name "unconnected-(P15-INT1-Pad6)") (class "Default")
      (node (ref "P15") (pin "6") (pinfunction "INT1_6") (pintype "output"))
    )
    (net (code "71") (name "unconnected-(P15-INT2-Pad5)") (class "Default")
      (node (ref "P15") (pin "5") (pinfunction "INT2_5") (pintype "output"))
    )
    (net (code "72") (name "unconnected-(P16-INT1-Pad6)") (class "Default")
      (node (ref "P16") (pin "6") (pinfunction "INT1_6") (pintype "output"))
    )
    (net (code "73") (name "unconnected-(P16-INT2-Pad5)") (class "Default")
      (node (ref "P16") (pin "5") (pinfunction "INT2_5") (pintype "output"))
    )
  )
)
